# Detector.net
KiCad netlist of a schematic drawn in Altium Designer
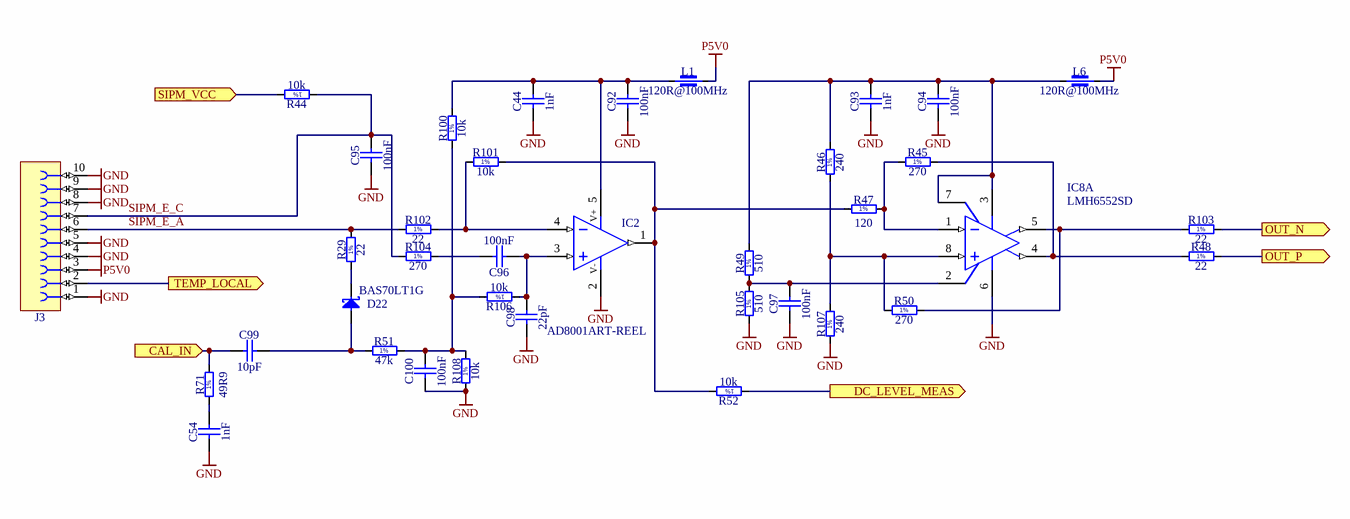
[diagram p0: Detector.SchDoc]

(export (version "E")
  (design (tool "Eeschema 10.0.6"))
  (components
    (comp (ref "C44")
      (value "1nF")
      (footprint "CAPC1608X87N")
      (description "Non-polarised capacitor")
      (fields
        (field (name "PART NUMBER") "CC0603_1NF_100V_10%_X7R")
        (field (name "VOLTAGE") "100V")
        (field (name "AUTHOR") "CERN DEM JLC")
      )
      (libsource (lib "Capacitors") (part "Capacitor - non polarized"))
    )
    (comp (ref "C54")
      (value "1nF")
      (footprint "CAPC1608X87N")
      (description "Non-polarised capacitor")
      (fields
        (field (name "PART NUMBER") "CC0603_1NF_100V_10%_X7R")
        (field (name "VOLTAGE") "100V")
        (field (name "AUTHOR") "CERN DEM JLC")
      )
      (libsource (lib "Capacitors") (part "Capacitor - non polarized"))
    )
    (comp (ref "C92")
      (value "100nF")
      (footprint "CAPC1005X55N")
      (description "Non-polarised capacitor")
      (fields
        (field (name "PART NUMBER") "CC0402_100NF_16V_10%_X7R")
        (field (name "VOLTAGE") "16V")
        (field (name "AUTHOR") "CERN DEM JLC")
      )
      (libsource (lib "Capacitors") (part "Capacitor - non polarized"))
    )
    (comp (ref "C93")
      (value "1nF")
      (footprint "CAPC1608X87N")
      (description "Non-polarised capacitor")
      (fields
        (field (name "PART NUMBER") "CC0603_1NF_100V_10%_X7R")
        (field (name "VOLTAGE") "100V")
        (field (name "AUTHOR") "CERN DEM JLC")
      )
      (libsource (lib "Capacitors") (part "Capacitor - non polarized"))
    )
    (comp (ref "C94")
      (value "100nF")
      (footprint "CAPC1005X55N")
      (description "Non-polarised capacitor")
      (fields
        (field (name "PART NUMBER") "CC0402_100NF_16V_10%_X7R")
        (field (name "VOLTAGE") "16V")
        (field (name "AUTHOR") "CERN DEM JLC")
      )
      (libsource (lib "Capacitors") (part "Capacitor - non polarized"))
    )
    (comp (ref "C95")
      (value "100nF")
      (footprint "CAPC1608X90N")
      (description "Non-polarised capacitor")
      (fields
        (field (name "PART NUMBER") "CC0603_100NF_100V_10%_X7R")
        (field (name "VOLTAGE") "100V")
        (field (name "AUTHOR") "CERN DEM JLC")
      )
      (libsource (lib "Capacitors") (part "Capacitor - non polarized"))
    )
    (comp (ref "C96")
      (value "100nF")
      (footprint "CAPC1608X90N")
      (description "Non-polarised capacitor")
      (fields
        (field (name "PART NUMBER") "CC0603_100NF_100V_10%_X7R")
        (field (name "VOLTAGE") "100V")
        (field (name "AUTHOR") "CERN DEM JLC")
      )
      (libsource (lib "Capacitors") (part "Capacitor - non polarized"))
    )
    (comp (ref "C97")
      (value "100nF")
      (footprint "CAPC1005X55N")
      (description "Non-polarised capacitor")
      (fields
        (field (name "PART NUMBER") "CC0402_100NF_16V_10%_X7R")
        (field (name "VOLTAGE") "16V")
        (field (name "AUTHOR") "CERN DEM JLC")
      )
      (libsource (lib "Capacitors") (part "Capacitor - non polarized"))
    )
    (comp (ref "C98")
      (value "22pF")
      (footprint "CAPC1005X55N")
      (description "Non-polarised capacitor")
      (fields
        (field (name "PART NUMBER") "CC0402_22PF_50V_5%_C0G")
        (field (name "VOLTAGE") "50V")
        (field (name "AUTHOR") "CERN DEM JLC")
      )
      (libsource (lib "Capacitors") (part "Capacitor - non polarized"))
    )
    (comp (ref "C99")
      (value "10pF")
      (footprint "CAPC1608X87N")
      (description "Non-polarised capacitor")
      (fields
        (field (name "PART NUMBER") "CC0603_10PF_50V_5%_NP0")
        (field (name "VOLTAGE") "50V")
        (field (name "AUTHOR") "CERN DEM JLC")
      )
      (libsource (lib "Capacitors") (part "Capacitor - non polarized"))
    )
    (comp (ref "C100")
      (value "100nF")
      (footprint "CAPC1005X55N")
      (description "Non-polarised capacitor")
      (fields
        (field (name "PART NUMBER") "CC0402_100NF_16V_10%_X7R")
        (field (name "VOLTAGE") "16V")
        (field (name "AUTHOR") "CERN DEM JLC")
      )
      (libsource (lib "Capacitors") (part "Capacitor - non polarized"))
    )
    (comp (ref "D22")
      (value "BAS70LT1G")
      (footprint "SOT95P240X110-3N")
      (description "Diode Schottky  Anode Pin 1 Cathode Pin 3 (Pas de pin 2)")
      (fields
        (field (name "VOLTAGE") "70V")
        (field (name "POWER") "70mA")
        (field (name "AUTHOR") "CERN DEM JLC")
      )
      (libsource (lib "ICs And Semiconductors") (part "Diode Schottky A1C3"))
    )
    (comp (ref "IC2")
      (value "AD8001ART-REEL")
      (footprint "SOT95P280X145-5N")
      (description "Operational Amplifier")
      (fields (field (name "MANUFACTURER") "ANALOG DEVICES") (field (name "AUTHOR") "CERN DEM JMW"))
      (libsource (lib "ICs And Semiconductors") (part "Operational Amplifier Type7"))
    )
    (comp (ref "IC8")
      (value "LMH6552SD")
      (footprint "SDA08C")
      (description "1.5 GHz Fully Differential Amplifier, 8-pin LLP")
      (fields (field (name "MANUFACTURER") "National Semiconductor"))
      (libsource (lib "Altium Content Vault") (part "AMP-DIFA-LMH6552-9"))
    )
    (comp (ref "J3")
      (value "FFC/FPC")
      (footprint "MOLEX_52745-1097")
      (description "Connector 10 Female")
      (fields
        (field (name "PART NUMBER") "MOLEX_52745-1097")
        (field (name "MANUFACTURER") "MOLEX")
        (field (name "AUTHOR") "CERN DEM JLC")
      )
      (libsource (lib "Connectors") (part "Connector 10 Female"))
    )
    (comp (ref "L1")
      (value "120R@100MHz")
      (footprint "INDC1005X55N")
      (fields
        (field (name "PART NUMBER") "IND0402_MURATA_BLM15PX121SN1D")
        (field (name "POWER") "2A")
        (field (name "TOLERANCE") "±25%")
        (field (name "AUTHOR") "CERN DEM JMW")
      )
      (libsource (lib "Inductors & Transformers") (part "Ferrite Bead"))
    )
    (comp (ref "L6")
      (value "120R@100MHz")
      (footprint "INDC1005X55N")
      (fields
        (field (name "PART NUMBER") "IND0402_MURATA_BLM15PX121SN1D")
        (field (name "POWER") "2A")
        (field (name "TOLERANCE") "±25%")
        (field (name "AUTHOR") "CERN DEM JMW")
      )
      (libsource (lib "Inductors & Transformers") (part "Ferrite Bead"))
    )
    (comp (ref "R29")
      (value "22")
      (footprint "RESC1608X55N")
      (description "Resistor - 1%")
      (fields
        (field (name "PART NUMBER") "R0603_22R_1%_0.1W_100PPM")
        (field (name "POWER") "0.1W")
        (field (name "AUTHOR") "CERN DEM JLC")
      )
      (libsource (lib "Resistors") (part "Resistor - 1%"))
    )
    (comp (ref "R44")
      (value "10k")
      (footprint "RESC1005X40N")
      (description "Resistor - 1%")
      (fields
        (field (name "PART NUMBER") "R0402_10K_1%_0.0625W_100PPM")
        (field (name "POWER") "0.0625W")
        (field (name "AUTHOR") "CERN DEM JLC")
      )
      (libsource (lib "Resistors") (part "Resistor - 1%"))
    )
    (comp (ref "R45")
      (value "270")
      (footprint "RESC1005X40N")
      (description "Resistor - 1%")
      (fields
        (field (name "PART NUMBER") "R0402_270R_1%_0.0625W_100PPM")
        (field (name "POWER") "0.0625W")
        (field (name "AUTHOR") "CERN DEM JLC")
      )
      (libsource (lib "Resistors") (part "Resistor - 1%"))
    )
    (comp (ref "R46")
      (value "240")
      (footprint "RESC1005X40N")
      (description "Resistor - 1%")
      (fields
        (field (name "PART NUMBER") "R0402_240R_1%_0.0625W_100PPM")
        (field (name "POWER") "0.0625W")
        (field (name "AUTHOR") "CERN DEM JLC")
      )
      (libsource (lib "Resistors") (part "Resistor - 1%"))
    )
    (comp (ref "R47")
      (value "120")
      (footprint "RESC1005X40N")
      (description "Resistor - 1%")
      (fields
        (field (name "PART NUMBER") "R0402_120R_1%_0.0625W_100PPM")
        (field (name "POWER") "0.0625W")
        (field (name "AUTHOR") "CERN DEM JLC")
      )
      (libsource (lib "Resistors") (part "Resistor - 1%"))
    )
    (comp (ref "R48")
      (value "22")
      (footprint "RESC1608X55N")
      (description "Resistor - 1%")
      (fields
        (field (name "PART NUMBER") "R0603_22R_1%_0.1W_100PPM")
        (field (name "POWER") "0.1W")
        (field (name "AUTHOR") "CERN DEM JLC")
      )
      (libsource (lib "Resistors") (part "Resistor - 1%"))
    )
    (comp (ref "R49")
      (value "510")
      (footprint "RESC1005X40N")
      (description "Resistor - 1%")
      (fields
        (field (name "PART NUMBER") "R0402_510R_1%_0.0625W_100PPM")
        (field (name "POWER") "0.0625W")
        (field (name "AUTHOR") "CERN DEM JLC")
      )
      (libsource (lib "Resistors") (part "Resistor - 1%"))
    )
    (comp (ref "R50")
      (value "270")
      (footprint "RESC1005X40N")
      (description "Resistor - 1%")
      (fields
        (field (name "PART NUMBER") "R0402_270R_1%_0.0625W_100PPM")
        (field (name "POWER") "0.0625W")
        (field (name "AUTHOR") "CERN DEM JLC")
      )
      (libsource (lib "Resistors") (part "Resistor - 1%"))
    )
    (comp (ref "R51")
      (value "47k")
      (footprint "RESC1005X40N")
      (description "Resistor - 1%")
      (fields
        (field (name "PART NUMBER") "R0402_47K_1%_0.0625W_100PPM")
        (field (name "POWER") "0.0625W")
        (field (name "AUTHOR") "CERN DEM JLC")
      )
      (libsource (lib "Resistors") (part "Resistor - 1%"))
    )
    (comp (ref "R52")
      (value "10k")
      (footprint "RESC1005X40N")
      (description "Resistor - 1%")
      (fields
        (field (name "PART NUMBER") "R0402_10K_1%_0.0625W_100PPM")
        (field (name "POWER") "0.0625W")
        (field (name "AUTHOR") "CERN DEM JLC")
      )
      (libsource (lib "Resistors") (part "Resistor - 1%"))
    )
    (comp (ref "R71")
      (value "49R9")
      (footprint "RESC1005X40N")
      (description "Resistor - 1%")
      (fields
        (field (name "PART NUMBER") "R0402_49R9_1%_0.0625W_100PPM")
        (field (name "POWER") "0.0625W")
        (field (name "AUTHOR") "CERN DEM JLC")
      )
      (libsource (lib "Resistors") (part "Resistor - 1%"))
    )
    (comp (ref "R100")
      (value "10k")
      (footprint "RESC1005X40N")
      (description "Resistor - 1%")
      (fields
        (field (name "PART NUMBER") "R0402_10K_1%_0.0625W_100PPM")
        (field (name "POWER") "0.0625W")
        (field (name "AUTHOR") "CERN DEM JLC")
      )
      (libsource (lib "Resistors") (part "Resistor - 1%"))
    )
    (comp (ref "R101")
      (value "10k")
      (footprint "RESC1005X40N")
      (description "Resistor - 1%")
      (fields
        (field (name "PART NUMBER") "R0402_10K_1%_0.0625W_100PPM")
        (field (name "POWER") "0.0625W")
        (field (name "AUTHOR") "CERN DEM JLC")
      )
      (libsource (lib "Resistors") (part "Resistor - 1%"))
    )
    (comp (ref "R102")
      (value "22")
      (footprint "RESC1608X55N")
      (description "Resistor - 1%")
      (fields
        (field (name "PART NUMBER") "R0603_22R_1%_0.1W_100PPM")
        (field (name "POWER") "0.1W")
        (field (name "AUTHOR") "CERN DEM JLC")
      )
      (libsource (lib "Resistors") (part "Resistor - 1%"))
    )
    (comp (ref "R103")
      (value "22")
      (footprint "RESC1608X55N")
      (description "Resistor - 1%")
      (fields
        (field (name "PART NUMBER") "R0603_22R_1%_0.1W_100PPM")
        (field (name "POWER") "0.1W")
        (field (name "AUTHOR") "CERN DEM JLC")
      )
      (libsource (lib "Resistors") (part "Resistor - 1%"))
    )
    (comp (ref "R104")
      (value "270")
      (footprint "RESC1005X40N")
      (description "Resistor - 1%")
      (fields
        (field (name "PART NUMBER") "R0402_270R_1%_0.0625W_100PPM")
        (field (name "POWER") "0.0625W")
        (field (name "AUTHOR") "CERN DEM JLC")
      )
      (libsource (lib "Resistors") (part "Resistor - 1%"))
    )
    (comp (ref "R105")
      (value "510")
      (footprint "RESC1005X40N")
      (description "Resistor - 1%")
      (fields
        (field (name "PART NUMBER") "R0402_510R_1%_0.0625W_100PPM")
        (field (name "POWER") "0.0625W")
        (field (name "AUTHOR") "CERN DEM JLC")
      )
      (libsource (lib "Resistors") (part "Resistor - 1%"))
    )
    (comp (ref "R106")
      (value "10k")
      (footprint "RESC1005X40N")
      (description "Resistor - 1%")
      (fields
        (field (name "PART NUMBER") "R0402_10K_1%_0.0625W_100PPM")
        (field (name "POWER") "0.0625W")
        (field (name "AUTHOR") "CERN DEM JLC")
      )
      (libsource (lib "Resistors") (part "Resistor - 1%"))
    )
    (comp (ref "R107")
      (value "240")
      (footprint "RESC1005X40N")
      (description "Resistor - 1%")
      (fields
        (field (name "PART NUMBER") "R0402_240R_1%_0.0625W_100PPM")
        (field (name "POWER") "0.0625W")
        (field (name "AUTHOR") "CERN DEM JLC")
      )
      (libsource (lib "Resistors") (part "Resistor - 1%"))
    )
    (comp (ref "R108")
      (value "10k")
      (footprint "RESC1005X40N")
      (description "Resistor - 1%")
      (fields
        (field (name "PART NUMBER") "R0402_10K_1%_0.0625W_100PPM")
        (field (name "POWER") "0.0625W")
        (field (name "AUTHOR") "CERN DEM JLC")
      )
      (libsource (lib "Resistors") (part "Resistor - 1%"))
    )
  )
  (nets
    (net (code "1") (name "/CAL_IN") (class "Default")
      (node (ref "C99") (pin "1") (pinfunction "1_1") (pintype "passive"))
      (node (ref "R71") (pin "2") (pinfunction "2_2") (pintype "passive"))
    )
    (net (code "2") (name "/DC_LEVEL_MEAS") (class "Default")
      (node (ref "R52") (pin "1") (pinfunction "1_1") (pintype "passive"))
    )
    (net (code "3") (name "/OUT_N") (class "Default")
      (node (ref "R103") (pin "2") (pinfunction "2_2") (pintype "passive"))
    )
    (net (code "4") (name "/OUT_P") (class "Default")
      (node (ref "R48") (pin "2") (pinfunction "2_2") (pintype "passive"))
    )
    (net (code "5") (name "/SIPM_E_A") (class "Default")
      (node (ref "J3") (pin "6") (pinfunction "6_6") (pintype "bidirectional"))
      (node (ref "R102") (pin "1") (pinfunction "1_1") (pintype "passive"))
      (node (ref "R29") (pin "2") (pinfunction "2_2") (pintype "passive"))
    )
    (net (code "6") (name "/SIPM_E_C") (class "Default")
      (node (ref "C95") (pin "2") (pinfunction "2_2") (pintype "passive"))
      (node (ref "J3") (pin "7") (pinfunction "7_7") (pintype "bidirectional"))
      (node (ref "R104") (pin "1") (pinfunction "1_1") (pintype "passive"))
      (node (ref "R44") (pin "1") (pinfunction "1_1") (pintype "passive"))
    )
    (net (code "7") (name "/SIPM_VCC") (class "Default")
      (node (ref "R44") (pin "2") (pinfunction "2_2") (pintype "passive"))
    )
    (net (code "8") (name "/TEMP_LOCAL") (class "Default")
      (node (ref "J3") (pin "2") (pinfunction "2_2") (pintype "bidirectional"))
    )
    (net (code "9") (name "GND") (class "Default")
      (node (ref "C100") (pin "1") (pinfunction "1_1") (pintype "passive"))
      (node (ref "C44") (pin "1") (pinfunction "1_1") (pintype "passive"))
      (node (ref "C54") (pin "1") (pinfunction "1_1") (pintype "passive"))
      (node (ref "C92") (pin "1") (pinfunction "1_1") (pintype "passive"))
      (node (ref "C93") (pin "1") (pinfunction "1_1") (pintype "passive"))
      (node (ref "C94") (pin "1") (pinfunction "1_1") (pintype "passive"))
      (node (ref "C95") (pin "1") (pinfunction "1_1") (pintype "passive"))
      (node (ref "C97") (pin "1") (pinfunction "1_1") (pintype "passive"))
      (node (ref "C98") (pin "1") (pinfunction "1_1") (pintype "passive"))
      (node (ref "IC2") (pin "2") (pinfunction "V-_2") (pintype "power_in"))
      (node (ref "IC8") (pin "6") (pinfunction "V-_6") (pintype "power_in"))
      (node (ref "J3") (pin "1") (pinfunction "1_1") (pintype "bidirectional"))
      (node (ref "J3") (pin "10") (pinfunction "10_10") (pintype "bidirectional"))
      (node (ref "J3") (pin "4") (pinfunction "4_4") (pintype "bidirectional"))
      (node (ref "J3") (pin "5") (pinfunction "5_5") (pintype "bidirectional"))
      (node (ref "J3") (pin "8") (pinfunction "8_8") (pintype "bidirectional"))
      (node (ref "J3") (pin "9") (pinfunction "9_9") (pintype "bidirectional"))
      (node (ref "R105") (pin "1") (pinfunction "1_1") (pintype "passive"))
      (node (ref "R107") (pin "1") (pinfunction "1_1") (pintype "passive"))
      (node (ref "R108") (pin "1") (pinfunction "1_1") (pintype "passive"))
    )
    (net (code "10") (name "Net-(C54-Pad2)") (class "Default")
      (node (ref "C54") (pin "2") (pinfunction "2_2") (pintype "passive"))
      (node (ref "R71") (pin "1") (pinfunction "1_1") (pintype "passive"))
    )
    (net (code "11") (name "Net-(C96-Pad2)") (class "Default")
      (node (ref "C96") (pin "2") (pinfunction "2_2") (pintype "passive"))
      (node (ref "R104") (pin "2") (pinfunction "2_2") (pintype "passive"))
    )
    (net (code "12") (name "Net-(C100-Pad2)") (class "Default")
      (node (ref "C100") (pin "2") (pinfunction "2_2") (pintype "passive"))
      (node (ref "R100") (pin "1") (pinfunction "1_1") (pintype "passive"))
      (node (ref "R106") (pin "2") (pinfunction "2_2") (pintype "passive"))
      (node (ref "R108") (pin "2") (pinfunction "2_2") (pintype "passive"))
      (node (ref "R51") (pin "2") (pinfunction "2_2") (pintype "passive"))
    )
    (net (code "13") (name "Net-(D22-A)") (class "Default")
      (node (ref "C99") (pin "2") (pinfunction "2_2") (pintype "passive"))
      (node (ref "D22") (pin "1") (pinfunction "A_1") (pintype "passive"))
      (node (ref "R51") (pin "1") (pinfunction "1_1") (pintype "passive"))
    )
    (net (code "14") (name "Net-(D22-C)") (class "Default")
      (node (ref "D22") (pin "3") (pinfunction "C_3") (pintype "passive"))
      (node (ref "R29") (pin "1") (pinfunction "1_1") (pintype "passive"))
    )
    (net (code "15") (name "Net-(IC2-IN+)") (class "Default")
      (node (ref "C96") (pin "1") (pinfunction "1_1") (pintype "passive"))
      (node (ref "C98") (pin "2") (pinfunction "2_2") (pintype "passive"))
      (node (ref "IC2") (pin "3") (pinfunction "IN+_3") (pintype "input"))
      (node (ref "R106") (pin "1") (pinfunction "1_1") (pintype "passive"))
    )
    (net (code "16") (name "Net-(IC2-IN-)") (class "Default")
      (node (ref "IC2") (pin "4") (pinfunction "IN-_4") (pintype "input"))
      (node (ref "R101") (pin "1") (pinfunction "1_1") (pintype "passive"))
      (node (ref "R102") (pin "2") (pinfunction "2_2") (pintype "passive"))
    )
    (net (code "17") (name "Net-(IC2-OUT)") (class "Default")
      (node (ref "IC2") (pin "1") (pinfunction "OUT_1") (pintype "output"))
      (node (ref "R101") (pin "2") (pinfunction "2_2") (pintype "passive"))
      (node (ref "R47") (pin "1") (pinfunction "1_1") (pintype "passive"))
      (node (ref "R52") (pin "2") (pinfunction "2_2") (pintype "passive"))
    )
    (net (code "18") (name "Net-(IC2-V+)") (class "Default")
      (node (ref "C44") (pin "2") (pinfunction "2_2") (pintype "passive"))
      (node (ref "C92") (pin "2") (pinfunction "2_2") (pintype "passive"))
      (node (ref "IC2") (pin "5") (pinfunction "V+_5") (pintype "power_in"))
      (node (ref "L1") (pin "1") (pinfunction "1_1") (pintype "passive"))
      (node (ref "R100") (pin "2") (pinfunction "2_2") (pintype "passive"))
    )
    (net (code "19") (name "Net-(IC8A-EN)") (class "Default")
      (node (ref "C93") (pin "2") (pinfunction "2_2") (pintype "passive"))
      (node (ref "C94") (pin "2") (pinfunction "2_2") (pintype "passive"))
      (node (ref "IC8") (pin "3") (pinfunction "V+_3") (pintype "power_in"))
      (node (ref "IC8") (pin "7") (pinfunction "EN_7") (pintype "passive"))
      (node (ref "L6") (pin "1") (pinfunction "1_1") (pintype "passive"))
      (node (ref "R46") (pin "2") (pinfunction "2_2") (pintype "passive"))
      (node (ref "R49") (pin "2") (pinfunction "2_2") (pintype "passive"))
    )
    (net (code "20") (name "Net-(IC8A-IN+)") (class "Default")
      (node (ref "IC8") (pin "8") (pinfunction "IN+_8") (pintype "input"))
      (node (ref "R107") (pin "2") (pinfunction "2_2") (pintype "passive"))
      (node (ref "R46") (pin "1") (pinfunction "1_1") (pintype "passive"))
      (node (ref "R50") (pin "1") (pinfunction "1_1") (pintype "passive"))
    )
    (net (code "21") (name "Net-(IC8A-IN-)") (class "Default")
      (node (ref "IC8") (pin "1") (pinfunction "IN-_1") (pintype "input"))
      (node (ref "R45") (pin "1") (pinfunction "1_1") (pintype "passive"))
      (node (ref "R47") (pin "2") (pinfunction "2_2") (pintype "passive"))
    )
    (net (code "22") (name "Net-(IC8A-OUT+)") (class "Default")
      (node (ref "IC8") (pin "4") (pinfunction "OUT+_4") (pintype "output"))
      (node (ref "R45") (pin "2") (pinfunction "2_2") (pintype "passive"))
      (node (ref "R48") (pin "1") (pinfunction "1_1") (pintype "passive"))
    )
    (net (code "23") (name "Net-(IC8A-OUT-)") (class "Default")
      (node (ref "IC8") (pin "5") (pinfunction "OUT-_5") (pintype "output"))
      (node (ref "R103") (pin "1") (pinfunction "1_1") (pintype "passive"))
      (node (ref "R50") (pin "2") (pinfunction "2_2") (pintype "passive"))
    )
    (net (code "24") (name "Net-(IC8A-VCM)") (class "Default")
      (node (ref "C97") (pin "2") (pinfunction "2_2") (pintype "passive"))
      (node (ref "IC8") (pin "2") (pinfunction "VCM_2") (pintype "passive"))
      (node (ref "R105") (pin "2") (pinfunction "2_2") (pintype "passive"))
      (node (ref "R49") (pin "1") (pinfunction "1_1") (pintype "passive"))
    )
    (net (code "25") (name "P5V0") (class "Default")
      (node (ref "J3") (pin "3") (pinfunction "3_3") (pintype "bidirectional"))
      (node (ref "L1") (pin "2") (pinfunction "2_2") (pintype "passive"))
      (node (ref "L6") (pin "2") (pinfunction "2_2") (pintype "passive"))
    )
  )
)
